# io.net
KiCad netlist of a schematic drawn in EAGLE
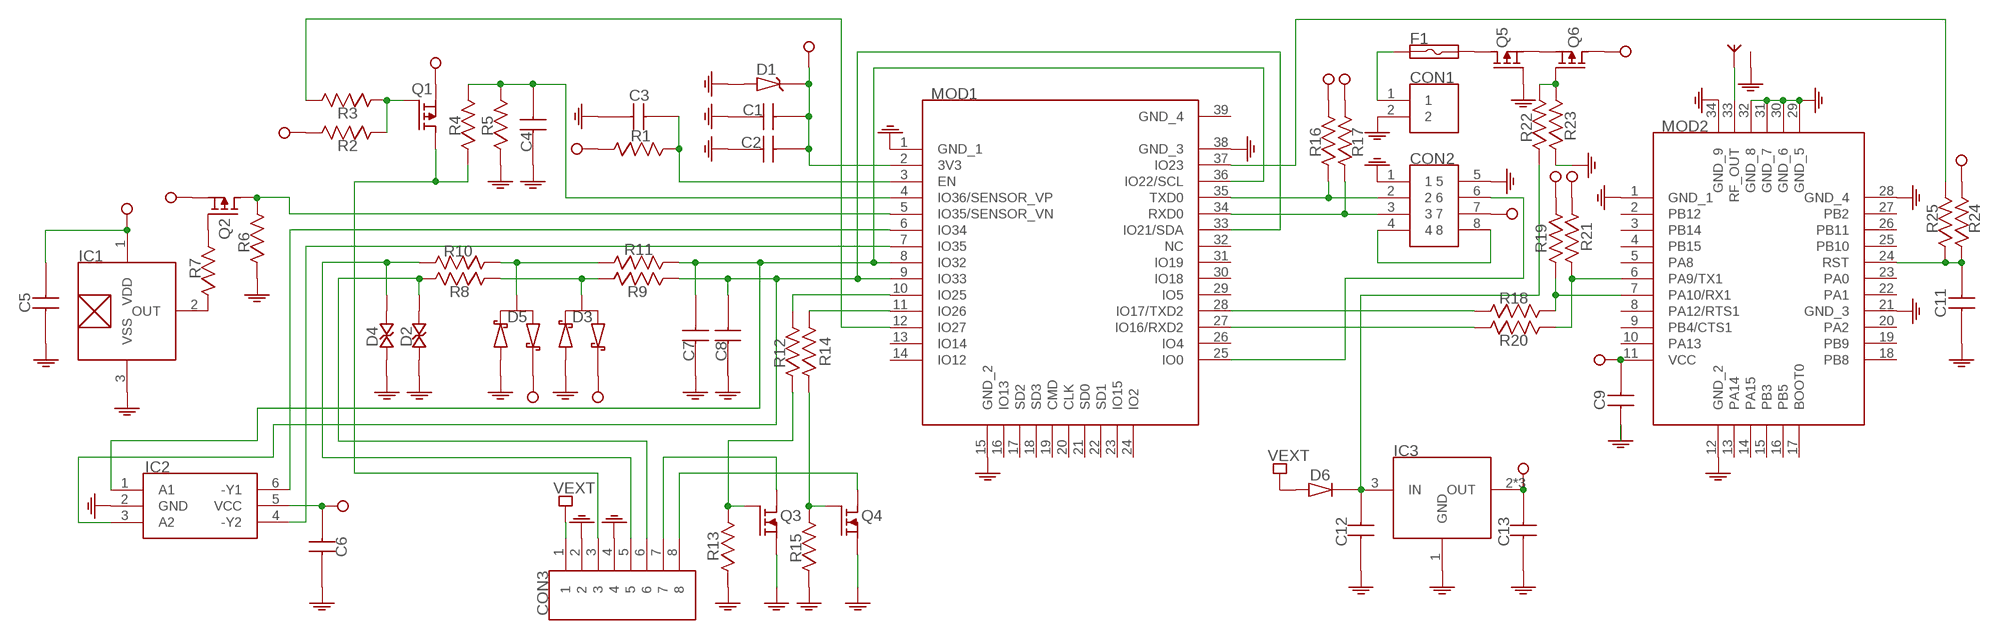
[diagram p0: schematic, sheet 1]

(export (version "E")
  (design (tool "Eeschema 10.0.6"))
  (components
    (comp (ref "ANT1")
      (value "SMA-RF")
      (footprint "eagle-import:SMA-RF")
      (libsource (lib "eagle-import") (part "SMA-RF"))
    )
    (comp (ref "C1")
      (value "CAPACITOR-0805")
      (footprint "eagle-import:0805")
      (libsource (lib "eagle-import") (part "CAPACITOR-0805"))
    )
    (comp (ref "C2")
      (value "CAPACITOR-0603")
      (footprint "eagle-import:0603")
      (libsource (lib "eagle-import") (part "CAPACITOR-0603"))
    )
    (comp (ref "C3")
      (value "CAPACITOR-0603")
      (footprint "eagle-import:0603")
      (libsource (lib "eagle-import") (part "CAPACITOR-0603"))
    )
    (comp (ref "C4")
      (value "CAPACITOR-0603")
      (footprint "eagle-import:0603")
      (libsource (lib "eagle-import") (part "CAPACITOR-0603"))
    )
    (comp (ref "C5")
      (value "CAPACITOR-0603")
      (footprint "eagle-import:0603")
      (libsource (lib "eagle-import") (part "CAPACITOR-0603"))
    )
    (comp (ref "C6")
      (value "CAPACITOR-0603")
      (footprint "eagle-import:0603")
      (libsource (lib "eagle-import") (part "CAPACITOR-0603"))
    )
    (comp (ref "C7")
      (value "CAPACITOR-0603")
      (footprint "eagle-import:0603")
      (libsource (lib "eagle-import") (part "CAPACITOR-0603"))
    )
    (comp (ref "C8")
      (value "CAPACITOR-0603")
      (footprint "eagle-import:0603")
      (libsource (lib "eagle-import") (part "CAPACITOR-0603"))
    )
    (comp (ref "C9")
      (value "CAPACITOR-0603")
      (footprint "eagle-import:0603")
      (libsource (lib "eagle-import") (part "CAPACITOR-0603"))
    )
    (comp (ref "C11")
      (value "CAPACITOR-0603")
      (footprint "eagle-import:0603")
      (libsource (lib "eagle-import") (part "CAPACITOR-0603"))
    )
    (comp (ref "C12")
      (value "CAPACITOR-0805")
      (footprint "eagle-import:0805")
      (libsource (lib "eagle-import") (part "CAPACITOR-0805"))
    )
    (comp (ref "C13")
      (value "CAPACITOR-0805")
      (footprint "eagle-import:0805")
      (libsource (lib "eagle-import") (part "CAPACITOR-0805"))
    )
    (comp (ref "CON1")
      (value "JST-PH-2-2.0MM")
      (footprint "eagle-import:JST-PH-2-2.0MM")
      (libsource (lib "eagle-import") (part "JST-PH-2-2.0MM"))
    )
    (comp (ref "CON2")
      (value "HEADER-8P-2R-DIP-2_0MM")
      (footprint "eagle-import:HEADER-8P-2R-DIP-2_0MM")
      (libsource (lib "eagle-import") (part "HEADER-8P-2R-DIP-2_0MM"))
    )
    (comp (ref "CON3")
      (value "CON-89-3_81-PLUG")
      (footprint "eagle-import:CON-8P-3_81-PLUG")
      (libsource (lib "eagle-import") (part "CON-89-3_81-PLUG"))
    )
    (comp (ref "D1")
      (value "ZENER-SOD123")
      (footprint "eagle-import:SOD123-DIODE")
      (libsource (lib "eagle-import") (part "ZENER-SOD123"))
    )
    (comp (ref "D2")
      (value "TVS-DIODE-SMA")
      (footprint "eagle-import:DO-214AC-SMA")
      (libsource (lib "eagle-import") (part "TVS-DIODE-SMA"))
    )
    (comp (ref "D3")
      (value "SCHOTTKY-SERIE-3P")
      (footprint "eagle-import:SOT23-3")
      (libsource (lib "eagle-import") (part "SCHOTTKY-SERIE-3P"))
    )
    (comp (ref "D4")
      (value "TVS-DIODE-SMA")
      (footprint "eagle-import:DO-214AC-SMA")
      (libsource (lib "eagle-import") (part "TVS-DIODE-SMA"))
    )
    (comp (ref "D5")
      (value "SCHOTTKY-SERIE-3P")
      (footprint "eagle-import:SOT23-3")
      (libsource (lib "eagle-import") (part "SCHOTTKY-SERIE-3P"))
    )
    (comp (ref "D6")
      (value "DIODE-DO-214AC-SMA")
      (footprint "eagle-import:DO-214AC-SMA-DIODE")
      (libsource (lib "eagle-import") (part "DIODE-DO-214AC-SMA"))
    )
    (comp (ref "F1")
      (value "FUSE-0805")
      (footprint "eagle-import:0805")
      (libsource (lib "eagle-import") (part "FUSE-0805"))
    )
    (comp (ref "IC1")
      (value "S-5712-SOT23-3")
      (footprint "eagle-import:SOT23-3")
      (libsource (lib "eagle-import") (part "S-5712-SOT23-3"))
    )
    (comp (ref "IC2")
      (value "NL27WZ04DTT1G")
      (footprint "eagle-import:SOT23-6")
      (libsource (lib "eagle-import") (part "NL27WZ04DTT1G"))
    )
    (comp (ref "IC3")
      (value "VREG-SOT-223")
      (footprint "eagle-import:SOT-223")
      (libsource (lib "eagle-import") (part "VREG-SOT-223"))
    )
    (comp (ref "MOD1")
      (value "ESP32-WROOM-32D")
      (footprint "eagle-import:ESP32-WROOM-32D")
      (libsource (lib "eagle-import") (part "ESP32-WROOM-32D"))
    )
    (comp (ref "MOD2")
      (value "RAK811")
      (footprint "eagle-import:RAK811")
      (libsource (lib "eagle-import") (part "RAK811"))
    )
    (comp (ref "Q1")
      (value "P-MOSFET")
      (footprint "eagle-import:SOT23-3")
      (libsource (lib "eagle-import") (part "P-MOSFET"))
    )
    (comp (ref "Q2")
      (value "P-MOSFET")
      (footprint "eagle-import:SOT23-3")
      (libsource (lib "eagle-import") (part "P-MOSFET"))
    )
    (comp (ref "Q3")
      (value "N-MOSFET")
      (footprint "eagle-import:SOT23-3")
      (libsource (lib "eagle-import") (part "N-MOSFET"))
    )
    (comp (ref "Q4")
      (value "N-MOSFET")
      (footprint "eagle-import:SOT23-3")
      (libsource (lib "eagle-import") (part "N-MOSFET"))
    )
    (comp (ref "Q5")
      (value "P-MOSFET")
      (footprint "eagle-import:SOT23-3")
      (libsource (lib "eagle-import") (part "P-MOSFET"))
    )
    (comp (ref "Q6")
      (value "P-MOSFET")
      (footprint "eagle-import:SOT23-3")
      (libsource (lib "eagle-import") (part "P-MOSFET"))
    )
    (comp (ref "R1")
      (value "RESISTOR-0603")
      (footprint "eagle-import:0603")
      (libsource (lib "eagle-import") (part "RESISTOR-0603"))
    )
    (comp (ref "R2")
      (value "RESISTOR-0603")
      (footprint "eagle-import:0603")
      (libsource (lib "eagle-import") (part "RESISTOR-0603"))
    )
    (comp (ref "R3")
      (value "RESISTOR-0603")
      (footprint "eagle-import:0603")
      (libsource (lib "eagle-import") (part "RESISTOR-0603"))
    )
    (comp (ref "R4")
      (value "RESISTOR-0603")
      (footprint "eagle-import:0603")
      (libsource (lib "eagle-import") (part "RESISTOR-0603"))
    )
    (comp (ref "R5")
      (value "RESISTOR-0603")
      (footprint "eagle-import:0603")
      (libsource (lib "eagle-import") (part "RESISTOR-0603"))
    )
    (comp (ref "R6")
      (value "RESISTOR-0603")
      (footprint "eagle-import:0603")
      (libsource (lib "eagle-import") (part "RESISTOR-0603"))
    )
    (comp (ref "R7")
      (value "RESISTOR-0603")
      (footprint "eagle-import:0603")
      (libsource (lib "eagle-import") (part "RESISTOR-0603"))
    )
    (comp (ref "R8")
      (value "RESISTOR-0805")
      (footprint "eagle-import:0805")
      (libsource (lib "eagle-import") (part "RESISTOR-0805"))
    )
    (comp (ref "R9")
      (value "RESISTOR-0603")
      (footprint "eagle-import:0603")
      (libsource (lib "eagle-import") (part "RESISTOR-0603"))
    )
    (comp (ref "R10")
      (value "RESISTOR-0805")
      (footprint "eagle-import:0805")
      (libsource (lib "eagle-import") (part "RESISTOR-0805"))
    )
    (comp (ref "R11")
      (value "RESISTOR-0603")
      (footprint "eagle-import:0603")
      (libsource (lib "eagle-import") (part "RESISTOR-0603"))
    )
    (comp (ref "R12")
      (value "RESISTOR-0603")
      (footprint "eagle-import:0603")
      (libsource (lib "eagle-import") (part "RESISTOR-0603"))
    )
    (comp (ref "R13")
      (value "RESISTOR-0603")
      (footprint "eagle-import:0603")
      (libsource (lib "eagle-import") (part "RESISTOR-0603"))
    )
    (comp (ref "R14")
      (value "RESISTOR-0603")
      (footprint "eagle-import:0603")
      (libsource (lib "eagle-import") (part "RESISTOR-0603"))
    )
    (comp (ref "R15")
      (value "RESISTOR-0603")
      (footprint "eagle-import:0603")
      (libsource (lib "eagle-import") (part "RESISTOR-0603"))
    )
    (comp (ref "R16")
      (value "RESISTOR-0603")
      (footprint "eagle-import:0603")
      (libsource (lib "eagle-import") (part "RESISTOR-0603"))
    )
    (comp (ref "R17")
      (value "RESISTOR-0603")
      (footprint "eagle-import:0603")
      (libsource (lib "eagle-import") (part "RESISTOR-0603"))
    )
    (comp (ref "R18")
      (value "RESISTOR-0603")
      (footprint "eagle-import:0603")
      (libsource (lib "eagle-import") (part "RESISTOR-0603"))
    )
    (comp (ref "R19")
      (value "RESISTOR-0603")
      (footprint "eagle-import:0603")
      (libsource (lib "eagle-import") (part "RESISTOR-0603"))
    )
    (comp (ref "R20")
      (value "RESISTOR-0603")
      (footprint "eagle-import:0603")
      (libsource (lib "eagle-import") (part "RESISTOR-0603"))
    )
    (comp (ref "R21")
      (value "RESISTOR-0603")
      (footprint "eagle-import:0603")
      (libsource (lib "eagle-import") (part "RESISTOR-0603"))
    )
    (comp (ref "R22")
      (value "RESISTOR-0603")
      (footprint "eagle-import:0603")
      (libsource (lib "eagle-import") (part "RESISTOR-0603"))
    )
    (comp (ref "R23")
      (value "RESISTOR-0603")
      (footprint "eagle-import:0603")
      (libsource (lib "eagle-import") (part "RESISTOR-0603"))
    )
    (comp (ref "R24")
      (value "RESISTOR-0603")
      (footprint "eagle-import:0603")
      (libsource (lib "eagle-import") (part "RESISTOR-0603"))
    )
    (comp (ref "R25")
      (value "RESISTOR-0603")
      (footprint "eagle-import:0603")
      (libsource (lib "eagle-import") (part "RESISTOR-0603"))
    )
  )
  (nets
    (net (code "1") (name "/GND_4") (class "Default")
      (node (ref "MOD1") (pin "39") (pinfunction "GND_4_39") (pintype "power_in"))
    )
    (net (code "2") (name "GND") (class "Default")
      (node (ref "ANT1") (pin "2") (pinfunction "GND_2") (pintype "power_in"))
      (node (ref "ANT1") (pin "3") (pinfunction "GND_3") (pintype "power_in"))
      (node (ref "ANT1") (pin "4") (pinfunction "GND_4") (pintype "power_in"))
      (node (ref "ANT1") (pin "5") (pinfunction "GND_5") (pintype "power_in"))
      (node (ref "C1") (pin "1") (pinfunction "1_1") (pintype "passive"))
      (node (ref "C11") (pin "1") (pinfunction "1_1") (pintype "passive"))
      (node (ref "C12") (pin "1") (pinfunction "1_1") (pintype "passive"))
      (node (ref "C13") (pin "1") (pinfunction "1_1") (pintype "passive"))
      (node (ref "C2") (pin "1") (pinfunction "1_1") (pintype "passive"))
      (node (ref "C3") (pin "1") (pinfunction "1_1") (pintype "passive"))
      (node (ref "C4") (pin "1") (pinfunction "1_1") (pintype "passive"))
      (node (ref "C5") (pin "1") (pinfunction "1_1") (pintype "passive"))
      (node (ref "C6") (pin "2") (pinfunction "2_2") (pintype "passive"))
      (node (ref "C7") (pin "1") (pinfunction "1_1") (pintype "passive"))
      (node (ref "C8") (pin "1") (pinfunction "1_1") (pintype "passive"))
      (node (ref "C9") (pin "1") (pinfunction "1_1") (pintype "passive"))
      (node (ref "CON1") (pin "2") (pinfunction "2_2") (pintype "bidirectional"))
      (node (ref "CON2") (pin "1") (pinfunction "1_1") (pintype "bidirectional"))
      (node (ref "CON2") (pin "5") (pinfunction "5_5") (pintype "bidirectional"))
      (node (ref "CON3") (pin "2") (pinfunction "2_2") (pintype "bidirectional"))
      (node (ref "CON3") (pin "4") (pinfunction "4_4") (pintype "bidirectional"))
      (node (ref "D1") (pin "2") (pinfunction "A_2") (pintype "bidirectional"))
      (node (ref "D2") (pin "1") (pinfunction "1_1") (pintype "bidirectional"))
      (node (ref "D3") (pin "1") (pinfunction "1_1") (pintype "bidirectional"))
      (node (ref "D4") (pin "1") (pinfunction "1_1") (pintype "bidirectional"))
      (node (ref "D5") (pin "1") (pinfunction "1_1") (pintype "bidirectional"))
      (node (ref "IC1") (pin "3") (pinfunction "VSS_3") (pintype "power_in"))
      (node (ref "IC2") (pin "2") (pinfunction "GND_2") (pintype "power_in"))
      (node (ref "IC3") (pin "1") (pinfunction "GND_1") (pintype "power_in"))
      (node (ref "MOD1") (pin "1") (pinfunction "GND_1_1") (pintype "power_in"))
      (node (ref "MOD1") (pin "15") (pinfunction "GND_2_15") (pintype "power_in"))
      (node (ref "MOD1") (pin "38") (pinfunction "GND_3_38") (pintype "power_in"))
      (node (ref "MOD2") (pin "1") (pinfunction "GND_1_1") (pintype "power_in"))
      (node (ref "MOD2") (pin "12") (pinfunction "GND_2_12") (pintype "power_in"))
      (node (ref "MOD2") (pin "21") (pinfunction "GND_3_21") (pintype "power_in"))
      (node (ref "MOD2") (pin "28") (pinfunction "GND_4_28") (pintype "power_in"))
      (node (ref "MOD2") (pin "29") (pinfunction "GND_5_29") (pintype "power_in"))
      (node (ref "MOD2") (pin "30") (pinfunction "GND_6_30") (pintype "power_in"))
      (node (ref "MOD2") (pin "31") (pinfunction "GND_7_31") (pintype "power_in"))
      (node (ref "MOD2") (pin "32") (pinfunction "GND_8_32") (pintype "power_in"))
      (node (ref "MOD2") (pin "34") (pinfunction "GND_9_34") (pintype "power_in"))
      (node (ref "Q3") (pin "2") (pinfunction "S_2") (pintype "bidirectional"))
      (node (ref "Q4") (pin "2") (pinfunction "S_2") (pintype "bidirectional"))
      (node (ref "Q5") (pin "1") (pinfunction "G_1") (pintype "bidirectional"))
      (node (ref "R13") (pin "1") (pinfunction "1_1") (pintype "passive"))
      (node (ref "R15") (pin "1") (pinfunction "1_1") (pintype "passive"))
      (node (ref "R23") (pin "1") (pinfunction "1_1") (pintype "passive"))
      (node (ref "R5") (pin "1") (pinfunction "1_1") (pintype "passive"))
      (node (ref "R6") (pin "1") (pinfunction "1_1") (pintype "passive"))
    )
    (net (code "3") (name "Net-(ANT1-ANT)") (class "Default")
      (node (ref "ANT1") (pin "1") (pinfunction "ANT_1") (pintype "bidirectional"))
      (node (ref "MOD2") (pin "33") (pinfunction "RF_OUT_33") (pintype "bidirectional"))
    )
    (net (code "4") (name "Net-(CON1-Pad1)") (class "Default")
      (node (ref "CON1") (pin "1") (pinfunction "1_1") (pintype "bidirectional"))
      (node (ref "F1") (pin "1") (pinfunction "1_1") (pintype "passive"))
    )
    (net (code "5") (name "Net-(CON2-Pad4)") (class "Default")
      (node (ref "CON2") (pin "4") (pinfunction "4_4") (pintype "bidirectional"))
      (node (ref "CON2") (pin "8") (pinfunction "8_8") (pintype "bidirectional"))
    )
    (net (code "6") (name "Net-(CON3-Pad5)") (class "Default")
      (node (ref "CON3") (pin "5") (pinfunction "5_5") (pintype "bidirectional"))
      (node (ref "D4") (pin "2") (pinfunction "2_2") (pintype "bidirectional"))
      (node (ref "R10") (pin "2") (pinfunction "2_2") (pintype "passive"))
    )
    (net (code "7") (name "Net-(CON3-Pad6)") (class "Default")
      (node (ref "CON3") (pin "6") (pinfunction "6_6") (pintype "bidirectional"))
      (node (ref "D2") (pin "2") (pinfunction "2_2") (pintype "bidirectional"))
      (node (ref "R8") (pin "2") (pinfunction "2_2") (pintype "passive"))
    )
    (net (code "8") (name "Net-(D3-Pad3)") (class "Default")
      (node (ref "D3") (pin "3") (pinfunction "3_3") (pintype "bidirectional"))
      (node (ref "R8") (pin "1") (pinfunction "1_1") (pintype "passive"))
      (node (ref "R9") (pin "1") (pinfunction "1_1") (pintype "passive"))
    )
    (net (code "9") (name "Net-(D5-Pad3)") (class "Default")
      (node (ref "D5") (pin "3") (pinfunction "3_3") (pintype "bidirectional"))
      (node (ref "R10") (pin "1") (pinfunction "1_1") (pintype "passive"))
      (node (ref "R11") (pin "1") (pinfunction "1_1") (pintype "passive"))
    )
    (net (code "10") (name "Net-(D6-K)") (class "Default")
      (node (ref "C12") (pin "2") (pinfunction "2_2") (pintype "passive"))
      (node (ref "D6") (pin "1") (pinfunction "K_1") (pintype "bidirectional"))
      (node (ref "IC3") (pin "3") (pinfunction "IN_3") (pintype "power_in"))
      (node (ref "R22") (pin "1") (pinfunction "1_1") (pintype "passive"))
    )
    (net (code "11") (name "Net-(IC1-OUT)") (class "Default")
      (node (ref "IC1") (pin "2") (pinfunction "OUT_2") (pintype "bidirectional"))
      (node (ref "R7") (pin "1") (pinfunction "1_1") (pintype "passive"))
    )
    (net (code "12") (name "Net-(IC2--Y1)") (class "Default")
      (node (ref "IC2") (pin "6") (pinfunction "-Y1_6") (pintype "power_in"))
      (node (ref "MOD1") (pin "6") (pinfunction "IO34_6") (pintype "bidirectional"))
    )
    (net (code "13") (name "Net-(IC2--Y2)") (class "Default")
      (node (ref "IC2") (pin "4") (pinfunction "-Y2_4") (pintype "bidirectional"))
      (node (ref "MOD1") (pin "7") (pinfunction "IO35_7") (pintype "bidirectional"))
    )
    (net (code "14") (name "Net-(IC2-A1)") (class "Default")
      (node (ref "C7") (pin "2") (pinfunction "2_2") (pintype "passive"))
      (node (ref "IC2") (pin "1") (pinfunction "A1_1") (pintype "bidirectional"))
      (node (ref "MOD1") (pin "36") (pinfunction "IO22/SCL_36") (pintype "bidirectional"))
      (node (ref "MOD1") (pin "8") (pinfunction "IO32_8") (pintype "bidirectional"))
      (node (ref "R11") (pin "2") (pinfunction "2_2") (pintype "passive"))
    )
    (net (code "15") (name "Net-(IC2-A2)") (class "Default")
      (node (ref "C8") (pin "2") (pinfunction "2_2") (pintype "passive"))
      (node (ref "IC2") (pin "3") (pinfunction "A2_3") (pintype "bidirectional"))
      (node (ref "MOD1") (pin "33") (pinfunction "IO21/SDA_33") (pintype "bidirectional"))
      (node (ref "MOD1") (pin "9") (pinfunction "IO33_9") (pintype "bidirectional"))
      (node (ref "R9") (pin "2") (pinfunction "2_2") (pintype "passive"))
    )
    (net (code "16") (name "Net-(MOD1-EN)") (class "Default")
      (node (ref "C3") (pin "2") (pinfunction "2_2") (pintype "passive"))
      (node (ref "MOD1") (pin "3") (pinfunction "EN_3") (pintype "bidirectional"))
      (node (ref "R1") (pin "2") (pinfunction "2_2") (pintype "passive"))
    )
    (net (code "17") (name "Net-(MOD1-IO0)") (class "Default")
      (node (ref "CON2") (pin "6") (pinfunction "6_6") (pintype "bidirectional"))
      (node (ref "MOD1") (pin "25") (pinfunction "IO0_25") (pintype "bidirectional"))
    )
    (net (code "18") (name "Net-(MOD1-IO16{slash}RXD2)") (class "Default")
      (node (ref "MOD1") (pin "27") (pinfunction "IO16/RXD2_27") (pintype "bidirectional"))
      (node (ref "R20") (pin "1") (pinfunction "1_1") (pintype "passive"))
    )
    (net (code "19") (name "Net-(MOD1-IO17{slash}TXD2)") (class "Default")
      (node (ref "MOD1") (pin "28") (pinfunction "IO17/TXD2_28") (pintype "bidirectional"))
      (node (ref "R18") (pin "1") (pinfunction "1_1") (pintype "passive"))
    )
    (net (code "20") (name "Net-(MOD1-IO23)") (class "Default")
      (node (ref "MOD1") (pin "37") (pinfunction "IO23_37") (pintype "bidirectional"))
      (node (ref "R25") (pin "2") (pinfunction "2_2") (pintype "passive"))
    )
    (net (code "21") (name "Net-(MOD1-IO25)") (class "Default")
      (node (ref "MOD1") (pin "10") (pinfunction "IO25_10") (pintype "bidirectional"))
      (node (ref "R12") (pin "2") (pinfunction "2_2") (pintype "passive"))
    )
    (net (code "22") (name "Net-(MOD1-IO26)") (class "Default")
      (node (ref "MOD1") (pin "11") (pinfunction "IO26_11") (pintype "bidirectional"))
      (node (ref "R14") (pin "2") (pinfunction "2_2") (pintype "passive"))
    )
    (net (code "23") (name "Net-(MOD1-IO27)") (class "Default")
      (node (ref "MOD1") (pin "12") (pinfunction "IO27_12") (pintype "bidirectional"))
      (node (ref "R3") (pin "2") (pinfunction "2_2") (pintype "passive"))
    )
    (net (code "24") (name "Net-(MOD1-IO35{slash}SENSOR_VN)") (class "Default")
      (node (ref "MOD1") (pin "5") (pinfunction "IO35/SENSOR_VN_5") (pintype "bidirectional"))
      (node (ref "Q2") (pin "3") (pinfunction "D_3") (pintype "bidirectional"))
      (node (ref "R6") (pin "2") (pinfunction "2_2") (pintype "passive"))
    )
    (net (code "25") (name "Net-(MOD1-IO36{slash}SENSOR_VP)") (class "Default")
      (node (ref "C4") (pin "2") (pinfunction "2_2") (pintype "passive"))
      (node (ref "MOD1") (pin "4") (pinfunction "IO36/SENSOR_VP_4") (pintype "bidirectional"))
      (node (ref "R4") (pin "2") (pinfunction "2_2") (pintype "passive"))
      (node (ref "R5") (pin "2") (pinfunction "2_2") (pintype "passive"))
    )
    (net (code "26") (name "Net-(MOD1-RXD0)") (class "Default")
      (node (ref "CON2") (pin "3") (pinfunction "3_3") (pintype "bidirectional"))
      (node (ref "MOD1") (pin "34") (pinfunction "RXD0_34") (pintype "bidirectional"))
      (node (ref "R17") (pin "1") (pinfunction "1_1") (pintype "passive"))
    )
    (net (code "27") (name "Net-(MOD1-TXD0)") (class "Default")
      (node (ref "CON2") (pin "2") (pinfunction "2_2") (pintype "bidirectional"))
      (node (ref "MOD1") (pin "35") (pinfunction "TXD0_35") (pintype "bidirectional"))
      (node (ref "R16") (pin "1") (pinfunction "1_1") (pintype "passive"))
    )
    (net (code "28") (name "Net-(MOD2-PA9{slash}TX1)") (class "Default")
      (node (ref "MOD2") (pin "6") (pinfunction "PA9/TX1_6") (pintype "bidirectional"))
      (node (ref "R20") (pin "2") (pinfunction "2_2") (pintype "passive"))
      (node (ref "R21") (pin "2") (pinfunction "2_2") (pintype "passive"))
    )
    (net (code "29") (name "Net-(MOD2-PA10{slash}RX1)") (class "Default")
      (node (ref "MOD2") (pin "7") (pinfunction "PA10/RX1_7") (pintype "bidirectional"))
      (node (ref "R18") (pin "2") (pinfunction "2_2") (pintype "passive"))
      (node (ref "R19") (pin "2") (pinfunction "2_2") (pintype "passive"))
    )
    (net (code "30") (name "Net-(MOD2-RST)") (class "Default")
      (node (ref "C11") (pin "2") (pinfunction "2_2") (pintype "passive"))
      (node (ref "MOD2") (pin "24") (pinfunction "RST_24") (pintype "bidirectional"))
      (node (ref "R24") (pin "1") (pinfunction "1_1") (pintype "passive"))
      (node (ref "R25") (pin "1") (pinfunction "1_1") (pintype "passive"))
    )
    (net (code "31") (name "Net-(Q1-D)") (class "Default")
      (node (ref "CON3") (pin "3") (pinfunction "3_3") (pintype "bidirectional"))
      (node (ref "Q1") (pin "3") (pinfunction "D_3") (pintype "bidirectional"))
      (node (ref "R4") (pin "1") (pinfunction "1_1") (pintype "passive"))
    )
    (net (code "32") (name "Net-(Q1-G)") (class "Default")
      (node (ref "Q1") (pin "1") (pinfunction "G_1") (pintype "bidirectional"))
      (node (ref "R2") (pin "1") (pinfunction "1_1") (pintype "passive"))
      (node (ref "R3") (pin "1") (pinfunction "1_1") (pintype "passive"))
    )
    (net (code "33") (name "Net-(Q2-G)") (class "Default")
      (node (ref "Q2") (pin "1") (pinfunction "G_1") (pintype "bidirectional"))
      (node (ref "R7") (pin "2") (pinfunction "2_2") (pintype "passive"))
    )
    (net (code "34") (name "Net-(Q3-D)") (class "Default")
      (node (ref "CON3") (pin "7") (pinfunction "7_7") (pintype "bidirectional"))
      (node (ref "Q3") (pin "3") (pinfunction "D_3") (pintype "bidirectional"))
    )
    (net (code "35") (name "Net-(Q3-G)") (class "Default")
      (node (ref "Q3") (pin "1") (pinfunction "G_1") (pintype "bidirectional"))
      (node (ref "R12") (pin "1") (pinfunction "1_1") (pintype "passive"))
      (node (ref "R13") (pin "2") (pinfunction "2_2") (pintype "passive"))
    )
    (net (code "36") (name "Net-(Q4-D)") (class "Default")
      (node (ref "CON3") (pin "8") (pinfunction "8_8") (pintype "bidirectional"))
      (node (ref "Q4") (pin "3") (pinfunction "D_3") (pintype "bidirectional"))
    )
    (net (code "37") (name "Net-(Q4-G)") (class "Default")
      (node (ref "Q4") (pin "1") (pinfunction "G_1") (pintype "bidirectional"))
      (node (ref "R14") (pin "1") (pinfunction "1_1") (pintype "passive"))
      (node (ref "R15") (pin "2") (pinfunction "2_2") (pintype "passive"))
    )
    (net (code "38") (name "Net-(Q5-D)") (class "Default")
      (node (ref "F1") (pin "2") (pinfunction "2_2") (pintype "passive"))
      (node (ref "Q5") (pin "3") (pinfunction "D_3") (pintype "bidirectional"))
    )
    (net (code "39") (name "Net-(Q5-S)") (class "Default")
      (node (ref "Q5") (pin "2") (pinfunction "S_2") (pintype "bidirectional"))
      (node (ref "Q6") (pin "2") (pinfunction "S_2") (pintype "bidirectional"))
    )
    (net (code "40") (name "Net-(Q6-G)") (class "Default")
      (node (ref "Q6") (pin "1") (pinfunction "G_1") (pintype "bidirectional"))
      (node (ref "R22") (pin "2") (pinfunction "2_2") (pintype "passive"))
      (node (ref "R23") (pin "2") (pinfunction "2_2") (pintype "passive"))
    )
    (net (code "41") (name "VCC") (class "Default")
      (node (ref "C1") (pin "2") (pinfunction "2_2") (pintype "passive"))
      (node (ref "C13") (pin "2") (pinfunction "2_2") (pintype "passive"))
      (node (ref "C2") (pin "2") (pinfunction "2_2") (pintype "passive"))
      (node (ref "C5") (pin "2") (pinfunction "2_2") (pintype "passive"))
      (node (ref "C6") (pin "1") (pinfunction "1_1") (pintype "passive"))
      (node (ref "C9") (pin "2") (pinfunction "2_2") (pintype "passive"))
      (node (ref "CON2") (pin "7") (pinfunction "7_7") (pintype "bidirectional"))
      (node (ref "D1") (pin "1") (pinfunction "K_1") (pintype "bidirectional"))
      (node (ref "D3") (pin "2") (pinfunction "2_2") (pintype "bidirectional"))
      (node (ref "D5") (pin "2") (pinfunction "2_2") (pintype "bidirectional"))
      (node (ref "IC1") (pin "1") (pinfunction "VDD_1") (pintype "power_in"))
      (node (ref "IC2") (pin "5") (pinfunction "VCC_5") (pintype "power_in"))
      (node (ref "IC3") (pin "2") (pinfunction "OUT_2") (pintype "power_in"))
      (node (ref "IC3") (pin "4") (pinfunction "OUT_4") (pintype "power_in"))
      (node (ref "IC3") (pin "5") (pinfunction "OUT_5") (pintype "power_in"))
      (node (ref "MOD1") (pin "2") (pinfunction "3V3_2") (pintype "power_in"))
      (node (ref "MOD2") (pin "11") (pinfunction "VCC_11") (pintype "power_in"))
      (node (ref "Q1") (pin "2") (pinfunction "S_2") (pintype "bidirectional"))
      (node (ref "Q2") (pin "2") (pinfunction "S_2") (pintype "bidirectional"))
      (node (ref "Q6") (pin "3") (pinfunction "D_3") (pintype "bidirectional"))
      (node (ref "R1") (pin "1") (pinfunction "1_1") (pintype "passive"))
      (node (ref "R16") (pin "2") (pinfunction "2_2") (pintype "passive"))
      (node (ref "R17") (pin "2") (pinfunction "2_2") (pintype "passive"))
      (node (ref "R19") (pin "1") (pinfunction "1_1") (pintype "passive"))
      (node (ref "R2") (pin "2") (pinfunction "2_2") (pintype "passive"))
      (node (ref "R21") (pin "1") (pinfunction "1_1") (pintype "passive"))
      (node (ref "R24") (pin "2") (pinfunction "2_2") (pintype "passive"))
    )
    (net (code "42") (name "VEXT") (class "Default")
      (node (ref "CON3") (pin "1") (pinfunction "1_1") (pintype "bidirectional"))
      (node (ref "D6") (pin "2") (pinfunction "A_2") (pintype "bidirectional"))
    )
    (net (code "43") (name "unconnected-(MOD1-CLK-Pad20)") (class "Default")
      (node (ref "MOD1") (pin "20") (pinfunction "CLK_20") (pintype "bidirectional"))
    )
    (net (code "44") (name "unconnected-(MOD1-CMD-Pad19)") (class "Default")
      (node (ref "MOD1") (pin "19") (pinfunction "CMD_19") (pintype "bidirectional"))
    )
    (net (code "45") (name "unconnected-(MOD1-IO2-Pad24)") (class "Default")
      (node (ref "MOD1") (pin "24") (pinfunction "IO2_24") (pintype "bidirectional"))
    )
    (net (code "46") (name "unconnected-(MOD1-IO4-Pad26)") (class "Default")
      (node (ref "MOD1") (pin "26") (pinfunction "IO4_26") (pintype "bidirectional"))
    )
    (net (code "47") (name "unconnected-(MOD1-IO5-Pad29)") (class "Default")
      (node (ref "MOD1") (pin "29") (pinfunction "IO5_29") (pintype "bidirectional"))
    )
    (net (code "48") (name "unconnected-(MOD1-IO12-Pad14)") (class "Default")
      (node (ref "MOD1") (pin "14") (pinfunction "IO12_14") (pintype "bidirectional"))
    )
    (net (code "49") (name "unconnected-(MOD1-IO13-Pad16)") (class "Default")
      (node (ref "MOD1") (pin "16") (pinfunction "IO13_16") (pintype "bidirectional"))
    )
    (net (code "50") (name "unconnected-(MOD1-IO14-Pad13)") (class "Default")
      (node (ref "MOD1") (pin "13") (pinfunction "IO14_13") (pintype "bidirectional"))
    )
    (net (code "51") (name "unconnected-(MOD1-IO15-Pad23)") (class "Default")
      (node (ref "MOD1") (pin "23") (pinfunction "IO15_23") (pintype "bidirectional"))
    )
    (net (code "52") (name "unconnected-(MOD1-IO18-Pad30)") (class "Default")
      (node (ref "MOD1") (pin "30") (pinfunction "IO18_30") (pintype "bidirectional"))
    )
    (net (code "53") (name "unconnected-(MOD1-IO19-Pad31)") (class "Default")
      (node (ref "MOD1") (pin "31") (pinfunction "IO19_31") (pintype "bidirectional"))
    )
    (net (code "54") (name "unconnected-(MOD1-NC-Pad32)") (class "Default")
      (node (ref "MOD1") (pin "32") (pinfunction "NC_32") (pintype "no_connect"))
    )
    (net (code "55") (name "unconnected-(MOD1-SD0-Pad21)") (class "Default")
      (node (ref "MOD1") (pin "21") (pinfunction "SD0_21") (pintype "bidirectional"))
    )
    (net (code "56") (name "unconnected-(MOD1-SD1-Pad22)") (class "Default")
      (node (ref "MOD1") (pin "22") (pinfunction "SD1_22") (pintype "bidirectional"))
    )
    (net (code "57") (name "unconnected-(MOD1-SD2-Pad17)") (class "Default")
      (node (ref "MOD1") (pin "17") (pinfunction "SD2_17") (pintype "bidirectional"))
    )
    (net (code "58") (name "unconnected-(MOD1-SD3-Pad18)") (class "Default")
      (node (ref "MOD1") (pin "18") (pinfunction "SD3_18") (pintype "bidirectional"))
    )
    (net (code "59") (name "unconnected-(MOD2-BOOT0-Pad17)") (class "Default")
      (node (ref "MOD2") (pin "17") (pinfunction "BOOT0_17") (pintype "bidirectional"))
    )
    (net (code "60") (name "unconnected-(MOD2-PA0-Pad23)") (class "Default")
      (node (ref "MOD2") (pin "23") (pinfunction "PA0_23") (pintype "bidirectional"))
    )
    (net (code "61") (name "unconnected-(MOD2-PA1-Pad22)") (class "Default")
      (node (ref "MOD2") (pin "22") (pinfunction "PA1_22") (pintype "bidirectional"))
    )
    (net (code "62") (name "unconnected-(MOD2-PA2-Pad20)") (class "Default")
      (node (ref "MOD2") (pin "20") (pinfunction "PA2_20") (pintype "bidirectional"))
    )
    (net (code "63") (name "unconnected-(MOD2-PA8-Pad5)") (class "Default")
      (node (ref "MOD2") (pin "5") (pinfunction "PA8_5") (pintype "bidirectional"))
    )
    (net (code "64") (name "unconnected-(MOD2-PA12{slash}RTS1-Pad8)") (class "Default")
      (node (ref "MOD2") (pin "8") (pinfunction "PA12/RTS1_8") (pintype "bidirectional"))
    )
    (net (code "65") (name "unconnected-(MOD2-PA13-Pad10)") (class "Default")
      (node (ref "MOD2") (pin "10") (pinfunction "PA13_10") (pintype "bidirectional"))
    )
    (net (code "66") (name "unconnected-(MOD2-PA14-Pad13)") (class "Default")
      (node (ref "MOD2") (pin "13") (pinfunction "PA14_13") (pintype "bidirectional"))
    )
    (net (code "67") (name "unconnected-(MOD2-PA15-Pad14)") (class "Default")
      (node (ref "MOD2") (pin "14") (pinfunction "PA15_14") (pintype "bidirectional"))
    )
    (net (code "68") (name "unconnected-(MOD2-PB2-Pad27)") (class "Default")
      (node (ref "MOD2") (pin "27") (pinfunction "PB2_27") (pintype "bidirectional"))
    )
    (net (code "69") (name "unconnected-(MOD2-PB3-Pad15)") (class "Default")
      (node (ref "MOD2") (pin "15") (pinfunction "PB3_15") (pintype "bidirectional"))
    )
    (net (code "70") (name "unconnected-(MOD2-PB4{slash}CTS1-Pad9)") (class "Default")
      (node (ref "MOD2") (pin "9") (pinfunction "PB4/CTS1_9") (pintype "bidirectional"))
    )
    (net (code "71") (name "unconnected-(MOD2-PB5-Pad16)") (class "Default")
      (node (ref "MOD2") (pin "16") (pinfunction "PB5_16") (pintype "bidirectional"))
    )
    (net (code "72") (name "unconnected-(MOD2-PB8-Pad18)") (class "Default")
      (node (ref "MOD2") (pin "18") (pinfunction "PB8_18") (pintype "bidirectional"))
    )
    (net (code "73") (name "unconnected-(MOD2-PB9-Pad19)") (class "Default")
      (node (ref "MOD2") (pin "19") (pinfunction "PB9_19") (pintype "bidirectional"))
    )
    (net (code "74") (name "unconnected-(MOD2-PB10-Pad25)") (class "Default")
      (node (ref "MOD2") (pin "25") (pinfunction "PB10_25") (pintype "bidirectional"))
    )
    (net (code "75") (name "unconnected-(MOD2-PB11-Pad26)") (class "Default")
      (node (ref "MOD2") (pin "26") (pinfunction "PB11_26") (pintype "bidirectional"))
    )
    (net (code "76") (name "unconnected-(MOD2-PB12-Pad2)") (class "Default")
      (node (ref "MOD2") (pin "2") (pinfunction "PB12_2") (pintype "bidirectional"))
    )
    (net (code "77") (name "unconnected-(MOD2-PB14-Pad3)") (class "Default")
      (node (ref "MOD2") (pin "3") (pinfunction "PB14_3") (pintype "bidirectional"))
    )
    (net (code "78") (name "unconnected-(MOD2-PB15-Pad4)") (class "Default")
      (node (ref "MOD2") (pin "4") (pinfunction "PB15_4") (pintype "bidirectional"))
    )
  )
)
